# logoi_smd_gndpln_v0_2.net
KiCad netlist of a schematic drawn in EAGLE
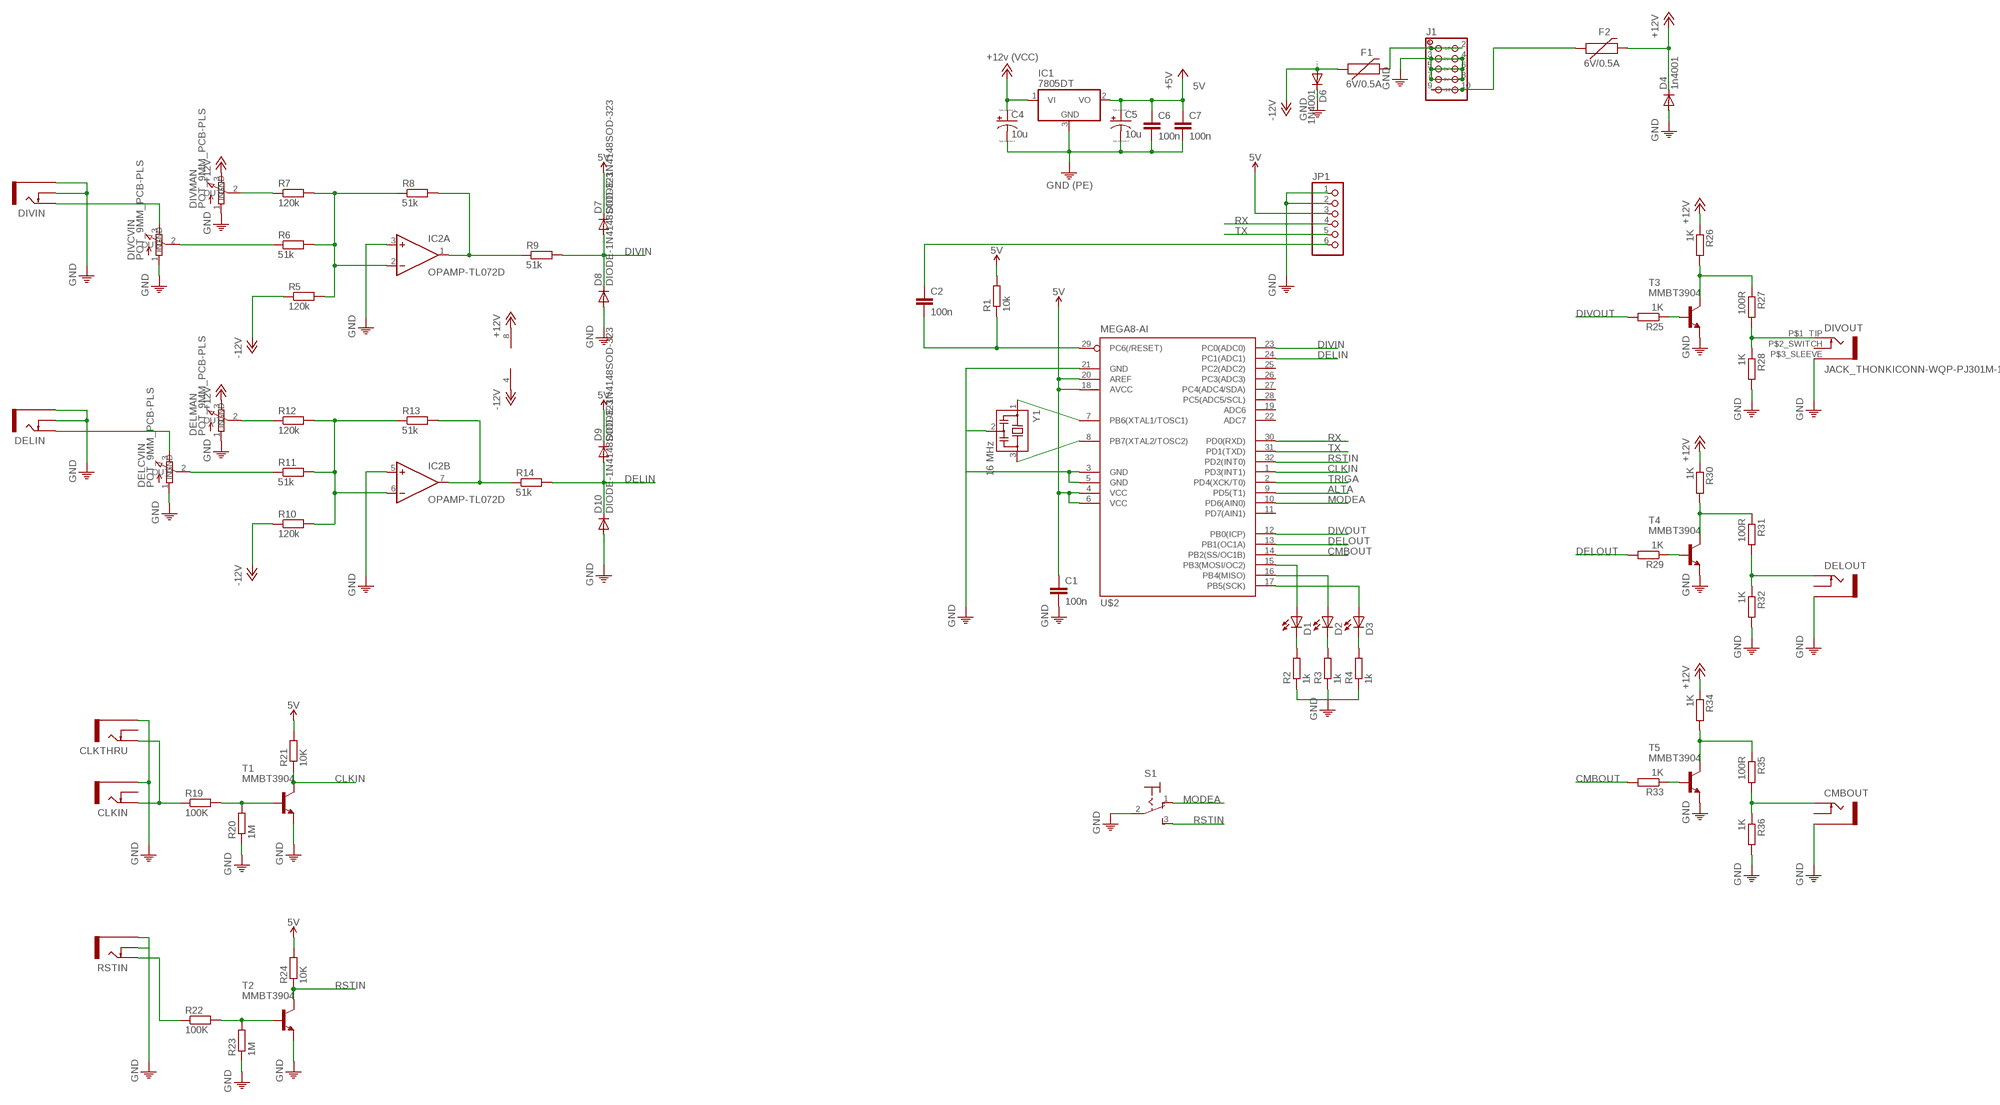
[diagram p0: schematic, sheet 1]

(export (version "E")
  (design (tool "Eeschema 10.0.6"))
  (components
    (comp (ref "C1")
      (value "100n")
      (footprint "eagle-import:C0603K")
      (libsource (lib "eagle-import") (part "CAPACITOR-EUC0603K"))
    )
    (comp (ref "C2")
      (value "100n")
      (footprint "eagle-import:C0603K")
      (libsource (lib "eagle-import") (part "CAPACITOR-EUC0603K"))
    )
    (comp (ref "C4")
      (value "10u")
      (footprint "eagle-import:PANASONIC_B")
      (libsource (lib "eagle-import") (part "CAPACITOR_POLARIZED-USB"))
    )
    (comp (ref "C5")
      (value "10u")
      (footprint "eagle-import:PANASONIC_B")
      (libsource (lib "eagle-import") (part "CAPACITOR_POLARIZED-USB"))
    )
    (comp (ref "C6")
      (value "100n")
      (footprint "eagle-import:C0603K")
      (libsource (lib "eagle-import") (part "CAPACITOR-EUC0603K"))
    )
    (comp (ref "C7")
      (value "100n")
      (footprint "eagle-import:C0603K")
      (libsource (lib "eagle-import") (part "CAPACITOR-EUC0603K"))
    )
    (comp (ref "CLKIN")
      (value "JACK_THONKICONNNEW")
      (footprint "eagle-import:WQP-PJ301M-12_JACK")
      (libsource (lib "eagle-import") (part "JACK_THONKICONNNEW"))
    )
    (comp (ref "CLKTHRU")
      (value "JACK_THONKICONNNEW")
      (footprint "eagle-import:WQP-PJ301M-12_JACK")
      (libsource (lib "eagle-import") (part "JACK_THONKICONNNEW"))
    )
    (comp (ref "CMBOUT")
      (value "JACK_THONKICONNNEW")
      (footprint "eagle-import:WQP-PJ301M-12_JACK")
      (libsource (lib "eagle-import") (part "JACK_THONKICONNNEW"))
    )
    (comp (ref "D1")
      (value "LED3MM")
      (footprint "eagle-import:LED3MM")
      (libsource (lib "eagle-import") (part "LED3MM"))
    )
    (comp (ref "D2")
      (value "LED3MM")
      (footprint "eagle-import:LED3MM")
      (libsource (lib "eagle-import") (part "LED3MM"))
    )
    (comp (ref "D3")
      (value "LED3MM")
      (footprint "eagle-import:LED3MM")
      (libsource (lib "eagle-import") (part "LED3MM"))
    )
    (comp (ref "D4")
      (value "1n4001")
      (footprint "eagle-import:DO-214AC")
      (libsource (lib "eagle-import") (part "DIODE-DO-214AC"))
    )
    (comp (ref "D6")
      (value "1N4001")
      (footprint "eagle-import:DO-214AC")
      (libsource (lib "eagle-import") (part "DIODE-DO-214AC"))
    )
    (comp (ref "D7")
      (value "DIODE-1N4148SOD-323")
      (footprint "eagle-import:SOD323W_INFINEON")
      (libsource (lib "eagle-import") (part "DIODE-1N4148SOD-323"))
    )
    (comp (ref "D8")
      (value "DIODE-1N4148SOD-323")
      (footprint "eagle-import:SOD323W_INFINEON")
      (libsource (lib "eagle-import") (part "DIODE-1N4148SOD-323"))
    )
    (comp (ref "D9")
      (value "DIODE-1N4148SOD-323")
      (footprint "eagle-import:SOD323W_INFINEON")
      (libsource (lib "eagle-import") (part "DIODE-1N4148SOD-323"))
    )
    (comp (ref "D10")
      (value "DIODE-1N4148SOD-323")
      (footprint "eagle-import:SOD323W_INFINEON")
      (libsource (lib "eagle-import") (part "DIODE-1N4148SOD-323"))
    )
    (comp (ref "DELCVIN")
      (value "POT_9MM_PCB-PLS")
      (footprint "eagle-import:9MM_PLS")
      (libsource (lib "eagle-import") (part "POT_9MM_PCB-PLS"))
    )
    (comp (ref "DELIN")
      (value "JACK_THONKICONNNEW")
      (footprint "eagle-import:WQP-PJ301M-12_JACK")
      (libsource (lib "eagle-import") (part "JACK_THONKICONNNEW"))
    )
    (comp (ref "DELMAN")
      (value "POT_9MM_PCB-PLS")
      (footprint "eagle-import:9MM_PLS")
      (libsource (lib "eagle-import") (part "POT_9MM_PCB-PLS"))
    )
    (comp (ref "DELOUT")
      (value "JACK_THONKICONNNEW")
      (footprint "eagle-import:WQP-PJ301M-12_JACK")
      (libsource (lib "eagle-import") (part "JACK_THONKICONNNEW"))
    )
    (comp (ref "DIVCVIN")
      (value "POT_9MM_PCB-PLS")
      (footprint "eagle-import:9MM_PLS")
      (libsource (lib "eagle-import") (part "POT_9MM_PCB-PLS"))
    )
    (comp (ref "DIVIN")
      (value "JACK_THONKICONNNEW")
      (footprint "eagle-import:WQP-PJ301M-12_JACK")
      (libsource (lib "eagle-import") (part "JACK_THONKICONNNEW"))
    )
    (comp (ref "DIVMAN")
      (value "POT_9MM_PCB-PLS")
      (footprint "eagle-import:9MM_PLS")
      (libsource (lib "eagle-import") (part "POT_9MM_PCB-PLS"))
    )
    (comp (ref "DIVOUT")
      (value "JACK_THONKICONN-WQP-PJ301M-12")
      (footprint "eagle-import:WQP-PJ301M-12_JACK")
      (libsource (lib "eagle-import") (part "JACK_THONKICONN-WQP-PJ301M-12"))
    )
    (comp (ref "F1")
      (value "6V/0.5A")
      (footprint "eagle-import:1206")
      (libsource (lib "eagle-import") (part "FUSE-PPTC_HALF-AMP"))
    )
    (comp (ref "F2")
      (value "6V/0.5A")
      (footprint "eagle-import:1206")
      (libsource (lib "eagle-import") (part "FUSE-PPTC_HALF-AMP"))
    )
    (comp (ref "IC1")
      (value "7805DT")
      (footprint "eagle-import:TO252")
      (libsource (lib "eagle-import") (part "78DT05"))
    )
    (comp (ref "IC2")
      (value "OPAMP-TL072D")
      (footprint "eagle-import:SO08")
      (libsource (lib "eagle-import") (part "OPAMP-TL072D"))
    )
    (comp (ref "J1")
      (value "HEADER-EUROPWR_2X05-OPEN")
      (footprint "eagle-import:2X05_EUROPWR_OPEN")
      (libsource (lib "eagle-import") (part "HEADER-EUROPWR_2X05-OPEN"))
    )
    (comp (ref "JP1")
      (value "PINHD-1X6")
      (footprint "eagle-import:1X06")
      (libsource (lib "eagle-import") (part "PINHD-1X6"))
    )
    (comp (ref "R1")
      (value "10k")
      (footprint "eagle-import:R0603")
      (libsource (lib "eagle-import") (part "RESISTOR-EU_R0603"))
    )
    (comp (ref "R2")
      (value "1k")
      (footprint "eagle-import:R0603")
      (libsource (lib "eagle-import") (part "RESISTOR-EU_R0603"))
    )
    (comp (ref "R3")
      (value "1k")
      (footprint "eagle-import:R0603")
      (libsource (lib "eagle-import") (part "RESISTOR-EU_R0603"))
    )
    (comp (ref "R4")
      (value "1k")
      (footprint "eagle-import:R0603")
      (libsource (lib "eagle-import") (part "RESISTOR-EU_R0603"))
    )
    (comp (ref "R5")
      (value "120k")
      (footprint "eagle-import:R0603")
      (libsource (lib "eagle-import") (part "RESISTOR-EU_R0603"))
    )
    (comp (ref "R6")
      (value "51k")
      (footprint "eagle-import:R0603")
      (libsource (lib "eagle-import") (part "RESISTOR-EU_R0603"))
    )
    (comp (ref "R7")
      (value "120k")
      (footprint "eagle-import:R0603")
      (libsource (lib "eagle-import") (part "RESISTOR-EU_R0603"))
    )
    (comp (ref "R8")
      (value "51k")
      (footprint "eagle-import:R0603")
      (libsource (lib "eagle-import") (part "RESISTOR-EU_R0603"))
    )
    (comp (ref "R9")
      (value "51k")
      (footprint "eagle-import:R0603")
      (libsource (lib "eagle-import") (part "RESISTOR-EU_R0603"))
    )
    (comp (ref "R10")
      (value "120k")
      (footprint "eagle-import:R0603")
      (libsource (lib "eagle-import") (part "RESISTOR-EU_R0603"))
    )
    (comp (ref "R11")
      (value "51k")
      (footprint "eagle-import:R0603")
      (libsource (lib "eagle-import") (part "RESISTOR-EU_R0603"))
    )
    (comp (ref "R12")
      (value "120k")
      (footprint "eagle-import:R0603")
      (libsource (lib "eagle-import") (part "RESISTOR-EU_R0603"))
    )
    (comp (ref "R13")
      (value "51k")
      (footprint "eagle-import:R0603")
      (libsource (lib "eagle-import") (part "RESISTOR-EU_R0603"))
    )
    (comp (ref "R14")
      (value "51k")
      (footprint "eagle-import:R0603")
      (libsource (lib "eagle-import") (part "RESISTOR-EU_R0603"))
    )
    (comp (ref "R19")
      (value "100K")
      (footprint "eagle-import:R0603")
      (libsource (lib "eagle-import") (part "RESISTOR-EU_R0603"))
    )
    (comp (ref "R20")
      (value "1M")
      (footprint "eagle-import:R0603")
      (libsource (lib "eagle-import") (part "RESISTOR-EU_R0603"))
    )
    (comp (ref "R21")
      (value "10K")
      (footprint "eagle-import:R0603")
      (libsource (lib "eagle-import") (part "RESISTOR-EU_R0603"))
    )
    (comp (ref "R22")
      (value "100K")
      (footprint "eagle-import:R0603")
      (libsource (lib "eagle-import") (part "RESISTOR-EU_R0603"))
    )
    (comp (ref "R23")
      (value "1M")
      (footprint "eagle-import:R0603")
      (libsource (lib "eagle-import") (part "RESISTOR-EU_R0603"))
    )
    (comp (ref "R24")
      (value "10K")
      (footprint "eagle-import:R0603")
      (libsource (lib "eagle-import") (part "RESISTOR-EU_R0603"))
    )
    (comp (ref "R25")
      (value "1K")
      (footprint "eagle-import:R0603")
      (libsource (lib "eagle-import") (part "RESISTOR-EU_R0603"))
    )
    (comp (ref "R26")
      (value "1K")
      (footprint "eagle-import:R0603")
      (libsource (lib "eagle-import") (part "RESISTOR-EU_R0603"))
    )
    (comp (ref "R27")
      (value "100R")
      (footprint "eagle-import:R0603")
      (libsource (lib "eagle-import") (part "RESISTOR-EU_R0603"))
    )
    (comp (ref "R28")
      (value "1K")
      (footprint "eagle-import:R0603")
      (libsource (lib "eagle-import") (part "RESISTOR-EU_R0603"))
    )
    (comp (ref "R29")
      (value "1K")
      (footprint "eagle-import:R0603")
      (libsource (lib "eagle-import") (part "RESISTOR-EU_R0603"))
    )
    (comp (ref "R30")
      (value "1K")
      (footprint "eagle-import:R0603")
      (libsource (lib "eagle-import") (part "RESISTOR-EU_R0603"))
    )
    (comp (ref "R31")
      (value "100R")
      (footprint "eagle-import:R0603")
      (libsource (lib "eagle-import") (part "RESISTOR-EU_R0603"))
    )
    (comp (ref "R32")
      (value "1K")
      (footprint "eagle-import:R0603")
      (libsource (lib "eagle-import") (part "RESISTOR-EU_R0603"))
    )
    (comp (ref "R33")
      (value "1K")
      (footprint "eagle-import:R0603")
      (libsource (lib "eagle-import") (part "RESISTOR-EU_R0603"))
    )
    (comp (ref "R34")
      (value "1K")
      (footprint "eagle-import:R0603")
      (libsource (lib "eagle-import") (part "RESISTOR-EU_R0603"))
    )
    (comp (ref "R35")
      (value "100R")
      (footprint "eagle-import:R0603")
      (libsource (lib "eagle-import") (part "RESISTOR-EU_R0603"))
    )
    (comp (ref "R36")
      (value "1K")
      (footprint "eagle-import:R0603")
      (libsource (lib "eagle-import") (part "RESISTOR-EU_R0603"))
    )
    (comp (ref "RSTIN")
      (value "JACK_THONKICONNNEW")
      (footprint "eagle-import:WQP-PJ301M-12_JACK")
      (libsource (lib "eagle-import") (part "JACK_THONKICONNNEW"))
    )
    (comp (ref "S1")
      (value "SWITCH-SPDT-320-916")
      (footprint "eagle-import:320-916")
      (libsource (lib "eagle-import") (part "SWITCH-SPDT-320-916"))
    )
    (comp (ref "T1")
      (value "MMBT3904")
      (footprint "eagle-import:SOT23-BEC")
      (libsource (lib "eagle-import") (part "TRANSISTOR-NPN-SOT23-BECMMBT3904LT1"))
    )
    (comp (ref "T2")
      (value "MMBT3904")
      (footprint "eagle-import:SOT23-BEC")
      (libsource (lib "eagle-import") (part "TRANSISTOR-NPN-SOT23-BECMMBT3904LT1"))
    )
    (comp (ref "T3")
      (value "MMBT3904")
      (footprint "eagle-import:SOT23-BEC")
      (libsource (lib "eagle-import") (part "TRANSISTOR-NPN-SOT23-BECMMBT3904LT1"))
    )
    (comp (ref "T4")
      (value "MMBT3904")
      (footprint "eagle-import:SOT23-BEC")
      (libsource (lib "eagle-import") (part "TRANSISTOR-NPN-SOT23-BECMMBT3904LT1"))
    )
    (comp (ref "T5")
      (value "MMBT3904")
      (footprint "eagle-import:SOT23-BEC")
      (libsource (lib "eagle-import") (part "TRANSISTOR-NPN-SOT23-BECMMBT3904LT1"))
    )
    (comp (ref "U$2")
      (value "MEGA8-AI")
      (footprint "eagle-import:TQFP32-08")
      (fields (field (name "MPN") "ATMEGA8-16AU"))
      (libsource (lib "eagle-import") (part "MEGA8-AI"))
    )
    (comp (ref "Y1")
      (value "16 MHz")
      (footprint "eagle-import:CSTCR6M")
      (fields (field (name "MPN") "CSTCR6M00G53-R0"))
      (libsource (lib "eagle-import") (part "CSTCR6M00G53Z"))
    )
  )
  (nets
    (net (code "1") (name "+5V") (class "Default")
      (node (ref "C1") (pin "1") (pinfunction "1_1") (pintype "passive"))
      (node (ref "C5") (pin "+") (pinfunction "+_+") (pintype "passive"))
      (node (ref "C6") (pin "1") (pinfunction "1_1") (pintype "passive"))
      (node (ref "C7") (pin "1") (pinfunction "1_1") (pintype "passive"))
      (node (ref "D7") (pin "C") (pinfunction "C_C") (pintype "passive"))
      (node (ref "D9") (pin "C") (pinfunction "C_C") (pintype "passive"))
      (node (ref "IC1") (pin "2") (pinfunction "VO_2") (pintype "passive"))
      (node (ref "JP1") (pin "3") (pinfunction "3_3") (pintype "passive"))
      (node (ref "R1") (pin "2") (pinfunction "2_2") (pintype "passive"))
      (node (ref "R21") (pin "2") (pinfunction "2_2") (pintype "passive"))
      (node (ref "R24") (pin "2") (pinfunction "2_2") (pintype "passive"))
      (node (ref "U$2") (pin "18") (pinfunction "AVCC_18") (pintype "power_in"))
      (node (ref "U$2") (pin "20") (pinfunction "AREF_20") (pintype "passive"))
      (node (ref "U$2") (pin "4") (pinfunction "VCC_4") (pintype "power_in"))
      (node (ref "U$2") (pin "6") (pinfunction "VCC_6") (pintype "power_in"))
    )
    (net (code "2") (name "+12V") (class "Default")
      (node (ref "C4") (pin "+") (pinfunction "+_+") (pintype "passive"))
      (node (ref "D4") (pin "C") (pinfunction "C_C") (pintype "passive"))
      (node (ref "DELMAN") (pin "3") (pinfunction "IN_3") (pintype "passive"))
      (node (ref "DIVMAN") (pin "3") (pinfunction "IN_3") (pintype "passive"))
      (node (ref "F2") (pin "2") (pinfunction "2_2") (pintype "bidirectional"))
      (node (ref "IC1") (pin "1") (pinfunction "VI_1") (pintype "input"))
      (node (ref "IC2") (pin "8") (pinfunction "V+_8") (pintype "power_in"))
      (node (ref "R26") (pin "1") (pinfunction "1_1") (pintype "passive"))
      (node (ref "R30") (pin "1") (pinfunction "1_1") (pintype "passive"))
      (node (ref "R34") (pin "1") (pinfunction "1_1") (pintype "passive"))
    )
    (net (code "3") (name "-12V") (class "Default")
      (node (ref "D6") (pin "A") (pinfunction "A_A") (pintype "passive"))
      (node (ref "F1") (pin "1") (pinfunction "1_1") (pintype "bidirectional"))
      (node (ref "IC2") (pin "4") (pinfunction "V-_4") (pintype "power_in"))
      (node (ref "R10") (pin "1") (pinfunction "1_1") (pintype "passive"))
      (node (ref "R5") (pin "1") (pinfunction "1_1") (pintype "passive"))
    )
    (net (code "4") (name "/ALTA") (class "Default")
      (node (ref "U$2") (pin "9") (pinfunction "PD5(T1)_9") (pintype "bidirectional"))
    )
    (net (code "5") (name "/CLKIN") (class "Default")
      (node (ref "R21") (pin "1") (pinfunction "1_1") (pintype "passive"))
      (node (ref "T1") (pin "C") (pinfunction "C_C") (pintype "passive"))
      (node (ref "U$2") (pin "1") (pinfunction "PD3(INT1)_1") (pintype "bidirectional"))
    )
    (net (code "6") (name "/CMBOUT") (class "Default")
      (node (ref "R33") (pin "2") (pinfunction "2_2") (pintype "passive"))
      (node (ref "U$2") (pin "14") (pinfunction "PB2(SS/OC1B)_14") (pintype "bidirectional"))
    )
    (net (code "7") (name "/DELIN") (class "Default")
      (node (ref "D10") (pin "C") (pinfunction "C_C") (pintype "passive"))
      (node (ref "D9") (pin "A") (pinfunction "A_A") (pintype "passive"))
      (node (ref "R14") (pin "2") (pinfunction "2_2") (pintype "passive"))
      (node (ref "U$2") (pin "24") (pinfunction "PC1(ADC1)_24") (pintype "bidirectional"))
    )
    (net (code "8") (name "/DELOUT") (class "Default")
      (node (ref "R29") (pin "2") (pinfunction "2_2") (pintype "passive"))
      (node (ref "U$2") (pin "13") (pinfunction "PB1(OC1A)_13") (pintype "bidirectional"))
    )
    (net (code "9") (name "/DIVIN") (class "Default")
      (node (ref "D7") (pin "A") (pinfunction "A_A") (pintype "passive"))
      (node (ref "D8") (pin "C") (pinfunction "C_C") (pintype "passive"))
      (node (ref "R9") (pin "2") (pinfunction "2_2") (pintype "passive"))
      (node (ref "U$2") (pin "23") (pinfunction "PC0(ADC0)_23") (pintype "bidirectional"))
    )
    (net (code "10") (name "/DIVOUT") (class "Default")
      (node (ref "R25") (pin "2") (pinfunction "2_2") (pintype "passive"))
      (node (ref "U$2") (pin "12") (pinfunction "PB0(ICP)_12") (pintype "bidirectional"))
    )
    (net (code "11") (name "/MODEA") (class "Default")
      (node (ref "S1") (pin "1") (pinfunction "O_1") (pintype "passive"))
      (node (ref "U$2") (pin "10") (pinfunction "PD6(AIN0)_10") (pintype "bidirectional"))
    )
    (net (code "12") (name "/RSTIN") (class "Default")
      (node (ref "R24") (pin "1") (pinfunction "1_1") (pintype "passive"))
      (node (ref "S1") (pin "3") (pinfunction "S_3") (pintype "passive"))
      (node (ref "T2") (pin "C") (pinfunction "C_C") (pintype "passive"))
      (node (ref "U$2") (pin "32") (pinfunction "PD2(INT0)_32") (pintype "bidirectional"))
    )
    (net (code "13") (name "/RX") (class "Default")
      (node (ref "JP1") (pin "4") (pinfunction "4_4") (pintype "passive"))
      (node (ref "U$2") (pin "30") (pinfunction "PD0(RXD)_30") (pintype "bidirectional"))
    )
    (net (code "14") (name "/TRIGA") (class "Default")
      (node (ref "U$2") (pin "2") (pinfunction "PD4(XCK/T0)_2") (pintype "bidirectional"))
    )
    (net (code "15") (name "/TX") (class "Default")
      (node (ref "JP1") (pin "5") (pinfunction "5_5") (pintype "passive"))
      (node (ref "U$2") (pin "31") (pinfunction "PD1(TXD)_31") (pintype "bidirectional"))
    )
    (net (code "16") (name "GND") (class "Default")
      (node (ref "C1") (pin "2") (pinfunction "2_2") (pintype "passive"))
      (node (ref "C4") (pin "-") (pinfunction "-_-") (pintype "passive"))
      (node (ref "C5") (pin "-") (pinfunction "-_-") (pintype "passive"))
      (node (ref "C6") (pin "2") (pinfunction "2_2") (pintype "passive"))
      (node (ref "C7") (pin "2") (pinfunction "2_2") (pintype "passive"))
      (node (ref "CLKIN") (pin "P$3_SLEEVE") (pinfunction "SLEEVE_P$3_SLEEVE") (pintype "passive"))
      (node (ref "CLKTHRU") (pin "P$3_SLEEVE") (pinfunction "SLEEVE_P$3_SLEEVE") (pintype "passive"))
      (node (ref "CMBOUT") (pin "P$3_SLEEVE") (pinfunction "SLEEVE_P$3_SLEEVE") (pintype "passive"))
      (node (ref "D10") (pin "A") (pinfunction "A_A") (pintype "passive"))
      (node (ref "D4") (pin "A") (pinfunction "A_A") (pintype "passive"))
      (node (ref "D6") (pin "C") (pinfunction "C_C") (pintype "passive"))
      (node (ref "D8") (pin "A") (pinfunction "A_A") (pintype "passive"))
      (node (ref "DELCVIN") (pin "1") (pinfunction "GND_1") (pintype "passive"))
      (node (ref "DELIN") (pin "P$2_SWITCH") (pinfunction "SWITCH_P$2_SWITCH") (pintype "passive"))
      (node (ref "DELIN") (pin "P$3_SLEEVE") (pinfunction "SLEEVE_P$3_SLEEVE") (pintype "passive"))
      (node (ref "DELMAN") (pin "1") (pinfunction "GND_1") (pintype "passive"))
      (node (ref "DELOUT") (pin "P$3_SLEEVE") (pinfunction "SLEEVE_P$3_SLEEVE") (pintype "passive"))
      (node (ref "DIVCVIN") (pin "1") (pinfunction "GND_1") (pintype "passive"))
      (node (ref "DIVIN") (pin "P$2_SWITCH") (pinfunction "SWITCH_P$2_SWITCH") (pintype "passive"))
      (node (ref "DIVIN") (pin "P$3_SLEEVE") (pinfunction "SLEEVE_P$3_SLEEVE") (pintype "passive"))
      (node (ref "DIVMAN") (pin "1") (pinfunction "GND_1") (pintype "passive"))
      (node (ref "DIVOUT") (pin "P$3_SLEEVE") (pinfunction "1_P$3_SLEEVE") (pintype "passive"))
      (node (ref "IC1") (pin "3") (pinfunction "GND_3") (pintype "passive"))
      (node (ref "IC2") (pin "3") (pinfunction "+IN_3") (pintype "input"))
      (node (ref "IC2") (pin "5") (pinfunction "+IN_5") (pintype "input"))
      (node (ref "J1") (pin "3") (pinfunction "3_3") (pintype "passive"))
      (node (ref "J1") (pin "4") (pinfunction "4_4") (pintype "passive"))
      (node (ref "J1") (pin "5") (pinfunction "5_5") (pintype "passive"))
      (node (ref "J1") (pin "6") (pinfunction "6_6") (pintype "passive"))
      (node (ref "J1") (pin "7") (pinfunction "7_7") (pintype "passive"))
      (node (ref "J1") (pin "8") (pinfunction "8_8") (pintype "passive"))
      (node (ref "JP1") (pin "1") (pinfunction "1_1") (pintype "passive"))
      (node (ref "JP1") (pin "2") (pinfunction "2_2") (pintype "passive"))
      (node (ref "R2") (pin "1") (pinfunction "1_1") (pintype "passive"))
      (node (ref "R20") (pin "1") (pinfunction "1_1") (pintype "passive"))
      (node (ref "R23") (pin "1") (pinfunction "1_1") (pintype "passive"))
      (node (ref "R28") (pin "2") (pinfunction "2_2") (pintype "passive"))
      (node (ref "R3") (pin "1") (pinfunction "1_1") (pintype "passive"))
      (node (ref "R32") (pin "2") (pinfunction "2_2") (pintype "passive"))
      (node (ref "R36") (pin "2") (pinfunction "2_2") (pintype "passive"))
      (node (ref "R4") (pin "1") (pinfunction "1_1") (pintype "passive"))
      (node (ref "RSTIN") (pin "P$2_SWITCH") (pinfunction "SWITCH_P$2_SWITCH") (pintype "passive"))
      (node (ref "RSTIN") (pin "P$3_SLEEVE") (pinfunction "SLEEVE_P$3_SLEEVE") (pintype "passive"))
      (node (ref "S1") (pin "2") (pinfunction "P_2") (pintype "passive"))
      (node (ref "T1") (pin "E") (pinfunction "E_E") (pintype "passive"))
      (node (ref "T2") (pin "E") (pinfunction "E_E") (pintype "passive"))
      (node (ref "T3") (pin "E") (pinfunction "E_E") (pintype "passive"))
      (node (ref "T4") (pin "E") (pinfunction "E_E") (pintype "passive"))
      (node (ref "T5") (pin "E") (pinfunction "E_E") (pintype "passive"))
      (node (ref "U$2") (pin "21") (pinfunction "GND_21") (pintype "power_in"))
      (node (ref "U$2") (pin "3") (pinfunction "GND_3") (pintype "power_in"))
      (node (ref "U$2") (pin "5") (pinfunction "GND_5") (pintype "power_in"))
      (node (ref "Y1") (pin "2") (pinfunction "2_2") (pintype "passive"))
    )
    (net (code "17") (name "Net-(C2-Pad1)") (class "Default")
      (node (ref "C2") (pin "1") (pinfunction "1_1") (pintype "passive"))
      (node (ref "JP1") (pin "6") (pinfunction "6_6") (pintype "passive"))
    )
    (net (code "18") (name "Net-(CLKIN-TIP)") (class "Default")
      (node (ref "CLKIN") (pin "P$1_TIP") (pinfunction "TIP_P$1_TIP") (pintype "passive"))
      (node (ref "CLKTHRU") (pin "P$1_TIP") (pinfunction "TIP_P$1_TIP") (pintype "passive"))
      (node (ref "R19") (pin "1") (pinfunction "1_1") (pintype "passive"))
    )
    (net (code "19") (name "Net-(CMBOUT-TIP)") (class "Default")
      (node (ref "CMBOUT") (pin "P$1_TIP") (pinfunction "TIP_P$1_TIP") (pintype "passive"))
      (node (ref "R35") (pin "2") (pinfunction "2_2") (pintype "passive"))
      (node (ref "R36") (pin "1") (pinfunction "1_1") (pintype "passive"))
    )
    (net (code "20") (name "Net-(D1-C)") (class "Default")
      (node (ref "D1") (pin "K") (pinfunction "C_K") (pintype "passive"))
      (node (ref "R2") (pin "2") (pinfunction "2_2") (pintype "passive"))
    )
    (net (code "21") (name "Net-(D2-C)") (class "Default")
      (node (ref "D2") (pin "K") (pinfunction "C_K") (pintype "passive"))
      (node (ref "R3") (pin "2") (pinfunction "2_2") (pintype "passive"))
    )
    (net (code "22") (name "Net-(D3-C)") (class "Default")
      (node (ref "D3") (pin "K") (pinfunction "C_K") (pintype "passive"))
      (node (ref "R4") (pin "2") (pinfunction "2_2") (pintype "passive"))
    )
    (net (code "23") (name "Net-(DELCVIN-IN)") (class "Default")
      (node (ref "DELCVIN") (pin "3") (pinfunction "IN_3") (pintype "passive"))
      (node (ref "DELIN") (pin "P$1_TIP") (pinfunction "TIP_P$1_TIP") (pintype "passive"))
    )
    (net (code "24") (name "Net-(DELCVIN-OUT)") (class "Default")
      (node (ref "DELCVIN") (pin "2") (pinfunction "OUT_2") (pintype "passive"))
      (node (ref "R11") (pin "1") (pinfunction "1_1") (pintype "passive"))
    )
    (net (code "25") (name "Net-(DELMAN-OUT)") (class "Default")
      (node (ref "DELMAN") (pin "2") (pinfunction "OUT_2") (pintype "passive"))
      (node (ref "R12") (pin "1") (pinfunction "1_1") (pintype "passive"))
    )
    (net (code "26") (name "Net-(DELOUT-TIP)") (class "Default")
      (node (ref "DELOUT") (pin "P$1_TIP") (pinfunction "TIP_P$1_TIP") (pintype "passive"))
      (node (ref "R31") (pin "2") (pinfunction "2_2") (pintype "passive"))
      (node (ref "R32") (pin "1") (pinfunction "1_1") (pintype "passive"))
    )
    (net (code "27") (name "Net-(DIVCVIN-IN)") (class "Default")
      (node (ref "DIVCVIN") (pin "3") (pinfunction "IN_3") (pintype "passive"))
      (node (ref "DIVIN") (pin "P$1_TIP") (pinfunction "TIP_P$1_TIP") (pintype "passive"))
    )
    (net (code "28") (name "Net-(DIVCVIN-OUT)") (class "Default")
      (node (ref "DIVCVIN") (pin "2") (pinfunction "OUT_2") (pintype "passive"))
      (node (ref "R6") (pin "1") (pinfunction "1_1") (pintype "passive"))
    )
    (net (code "29") (name "Net-(DIVMAN-OUT)") (class "Default")
      (node (ref "DIVMAN") (pin "2") (pinfunction "OUT_2") (pintype "passive"))
      (node (ref "R7") (pin "1") (pinfunction "1_1") (pintype "passive"))
    )
    (net (code "30") (name "Net-(DIVOUT-2)") (class "Default")
      (node (ref "DIVOUT") (pin "P$1_TIP") (pinfunction "2_P$1_TIP") (pintype "passive"))
      (node (ref "R27") (pin "2") (pinfunction "2_2") (pintype "passive"))
      (node (ref "R28") (pin "1") (pinfunction "1_1") (pintype "passive"))
    )
    (net (code "31") (name "Net-(F1-Pad2)") (class "Default")
      (node (ref "F1") (pin "2") (pinfunction "2_2") (pintype "bidirectional"))
      (node (ref "J1") (pin "1") (pinfunction "1_1") (pintype "passive"))
      (node (ref "J1") (pin "2") (pinfunction "2_2") (pintype "passive"))
    )
    (net (code "32") (name "Net-(F2-Pad1)") (class "Default")
      (node (ref "F2") (pin "1") (pinfunction "1_1") (pintype "bidirectional"))
      (node (ref "J1") (pin "10") (pinfunction "10_10") (pintype "passive"))
      (node (ref "J1") (pin "9") (pinfunction "9_9") (pintype "passive"))
    )
    (net (code "33") (name "Net-(IC2A--IN)") (class "Default")
      (node (ref "IC2") (pin "2") (pinfunction "-IN_2") (pintype "input"))
      (node (ref "R5") (pin "2") (pinfunction "2_2") (pintype "passive"))
      (node (ref "R6") (pin "2") (pinfunction "2_2") (pintype "passive"))
      (node (ref "R7") (pin "2") (pinfunction "2_2") (pintype "passive"))
      (node (ref "R8") (pin "1") (pinfunction "1_1") (pintype "passive"))
    )
    (net (code "34") (name "Net-(IC2A-OUT)") (class "Default")
      (node (ref "IC2") (pin "1") (pinfunction "OUT_1") (pintype "output"))
      (node (ref "R8") (pin "2") (pinfunction "2_2") (pintype "passive"))
      (node (ref "R9") (pin "1") (pinfunction "1_1") (pintype "passive"))
    )
    (net (code "35") (name "Net-(IC2B--IN)") (class "Default")
      (node (ref "IC2") (pin "6") (pinfunction "-IN_6") (pintype "input"))
      (node (ref "R10") (pin "2") (pinfunction "2_2") (pintype "passive"))
      (node (ref "R11") (pin "2") (pinfunction "2_2") (pintype "passive"))
      (node (ref "R12") (pin "2") (pinfunction "2_2") (pintype "passive"))
      (node (ref "R13") (pin "1") (pinfunction "1_1") (pintype "passive"))
    )
    (net (code "36") (name "Net-(IC2B-OUT)") (class "Default")
      (node (ref "IC2") (pin "7") (pinfunction "OUT_7") (pintype "output"))
      (node (ref "R13") (pin "2") (pinfunction "2_2") (pintype "passive"))
      (node (ref "R14") (pin "1") (pinfunction "1_1") (pintype "passive"))
    )
    (net (code "37") (name "Net-(R19-Pad2)") (class "Default")
      (node (ref "R19") (pin "2") (pinfunction "2_2") (pintype "passive"))
      (node (ref "R20") (pin "2") (pinfunction "2_2") (pintype "passive"))
      (node (ref "T1") (pin "B") (pinfunction "B_B") (pintype "passive"))
    )
    (net (code "38") (name "Net-(R22-Pad2)") (class "Default")
      (node (ref "R22") (pin "2") (pinfunction "2_2") (pintype "passive"))
      (node (ref "R23") (pin "2") (pinfunction "2_2") (pintype "passive"))
      (node (ref "T2") (pin "B") (pinfunction "B_B") (pintype "passive"))
    )
    (net (code "39") (name "Net-(R25-Pad1)") (class "Default")
      (node (ref "R25") (pin "1") (pinfunction "1_1") (pintype "passive"))
      (node (ref "T3") (pin "B") (pinfunction "B_B") (pintype "passive"))
    )
    (net (code "40") (name "Net-(R26-Pad2)") (class "Default")
      (node (ref "R26") (pin "2") (pinfunction "2_2") (pintype "passive"))
      (node (ref "R27") (pin "1") (pinfunction "1_1") (pintype "passive"))
      (node (ref "T3") (pin "C") (pinfunction "C_C") (pintype "passive"))
    )
    (net (code "41") (name "Net-(R29-Pad1)") (class "Default")
      (node (ref "R29") (pin "1") (pinfunction "1_1") (pintype "passive"))
      (node (ref "T4") (pin "B") (pinfunction "B_B") (pintype "passive"))
    )
    (net (code "42") (name "Net-(R30-Pad2)") (class "Default")
      (node (ref "R30") (pin "2") (pinfunction "2_2") (pintype "passive"))
      (node (ref "R31") (pin "1") (pinfunction "1_1") (pintype "passive"))
      (node (ref "T4") (pin "C") (pinfunction "C_C") (pintype "passive"))
    )
    (net (code "43") (name "Net-(R33-Pad1)") (class "Default")
      (node (ref "R33") (pin "1") (pinfunction "1_1") (pintype "passive"))
      (node (ref "T5") (pin "B") (pinfunction "B_B") (pintype "passive"))
    )
    (net (code "44") (name "Net-(R34-Pad2)") (class "Default")
      (node (ref "R34") (pin "2") (pinfunction "2_2") (pintype "passive"))
      (node (ref "R35") (pin "1") (pinfunction "1_1") (pintype "passive"))
      (node (ref "T5") (pin "C") (pinfunction "C_C") (pintype "passive"))
    )
    (net (code "45") (name "Net-(RSTIN-TIP)") (class "Default")
      (node (ref "R22") (pin "1") (pinfunction "1_1") (pintype "passive"))
      (node (ref "RSTIN") (pin "P$1_TIP") (pinfunction "TIP_P$1_TIP") (pintype "passive"))
    )
    (net (code "46") (name "Net-(U$2-PB3(MOSI{slash}OC2))") (class "Default")
      (node (ref "D1") (pin "A") (pinfunction "A_A") (pintype "passive"))
      (node (ref "U$2") (pin "15") (pinfunction "PB3(MOSI/OC2)_15") (pintype "bidirectional"))
    )
    (net (code "47") (name "Net-(U$2-PB4(MISO))") (class "Default")
      (node (ref "D2") (pin "A") (pinfunction "A_A") (pintype "passive"))
      (node (ref "U$2") (pin "16") (pinfunction "PB4(MISO)_16") (pintype "bidirectional"))
    )
    (net (code "48") (name "Net-(U$2-PB5(SCK))") (class "Default")
      (node (ref "D3") (pin "A") (pinfunction "A_A") (pintype "passive"))
      (node (ref "U$2") (pin "17") (pinfunction "PB5(SCK)_17") (pintype "bidirectional"))
    )
    (net (code "49") (name "Net-(U$2-PB6(XTAL1{slash}TOSC1))") (class "Default")
      (node (ref "U$2") (pin "7") (pinfunction "PB6(XTAL1/TOSC1)_7") (pintype "bidirectional"))
      (node (ref "Y1") (pin "1") (pinfunction "1_1") (pintype "passive"))
    )
    (net (code "50") (name "Net-(U$2-PB7(XTAL2{slash}TOSC2))") (class "Default")
      (node (ref "U$2") (pin "8") (pinfunction "PB7(XTAL2/TOSC2)_8") (pintype "bidirectional"))
      (node (ref "Y1") (pin "3") (pinfunction "3_3") (pintype "passive"))
    )
    (net (code "51") (name "Net-(U$2-PC6({slash}RESET))") (class "Default")
      (node (ref "C2") (pin "2") (pinfunction "2_2") (pintype "passive"))
      (node (ref "R1") (pin "1") (pinfunction "1_1") (pintype "passive"))
      (node (ref "U$2") (pin "29") (pinfunction "PC6(/RESET)_29") (pintype "bidirectional"))
    )
    (net (code "52") (name "unconnected-(CLKIN-SWITCH-PadP$2_SWITCH)") (class "Default")
      (node (ref "CLKIN") (pin "P$2_SWITCH") (pinfunction "SWITCH_P$2_SWITCH") (pintype "passive"))
    )
    (net (code "53") (name "unconnected-(CLKTHRU-SWITCH-PadP$2_SWITCH)") (class "Default")
      (node (ref "CLKTHRU") (pin "P$2_SWITCH") (pinfunction "SWITCH_P$2_SWITCH") (pintype "passive"))
    )
    (net (code "54") (name "unconnected-(CMBOUT-SWITCH-PadP$2_SWITCH)") (class "Default")
      (node (ref "CMBOUT") (pin "P$2_SWITCH") (pinfunction "SWITCH_P$2_SWITCH") (pintype "passive"))
    )
    (net (code "55") (name "unconnected-(DELOUT-SWITCH-PadP$2_SWITCH)") (class "Default")
      (node (ref "DELOUT") (pin "P$2_SWITCH") (pinfunction "SWITCH_P$2_SWITCH") (pintype "passive"))
    )
    (net (code "56") (name "unconnected-(DIVOUT-3-PadP$2_SWITCH)") (class "Default")
      (node (ref "DIVOUT") (pin "P$2_SWITCH") (pinfunction "3_P$2_SWITCH") (pintype "passive"))
    )
    (net (code "57") (name "unconnected-(U$2-ADC6-Pad19)") (class "Default")
      (node (ref "U$2") (pin "19") (pinfunction "ADC6_19") (pintype "bidirectional"))
    )
    (net (code "58") (name "unconnected-(U$2-ADC7-Pad22)") (class "Default")
      (node (ref "U$2") (pin "22") (pinfunction "ADC7_22") (pintype "bidirectional"))
    )
    (net (code "59") (name "unconnected-(U$2-PC2(ADC2)-Pad25)") (class "Default")
      (node (ref "U$2") (pin "25") (pinfunction "PC2(ADC2)_25") (pintype "bidirectional"))
    )
    (net (code "60") (name "unconnected-(U$2-PC3(ADC3)-Pad26)") (class "Default")
      (node (ref "U$2") (pin "26") (pinfunction "PC3(ADC3)_26") (pintype "bidirectional"))
    )
    (net (code "61") (name "unconnected-(U$2-PC4(ADC4{slash}SDA)-Pad27)") (class "Default")
      (node (ref "U$2") (pin "27") (pinfunction "PC4(ADC4/SDA)_27") (pintype "bidirectional"))
    )
    (net (code "62") (name "unconnected-(U$2-PC5(ADC5{slash}SCL)-Pad28)") (class "Default")
      (node (ref "U$2") (pin "28") (pinfunction "PC5(ADC5/SCL)_28") (pintype "bidirectional"))
    )
    (net (code "63") (name "unconnected-(U$2-PD7(AIN1)-Pad11)") (class "Default")
      (node (ref "U$2") (pin "11") (pinfunction "PD7(AIN1)_11") (pintype "bidirectional"))
    )
  )
)
